# Sheet2.net
KiCad netlist of a schematic drawn in Altium Designer
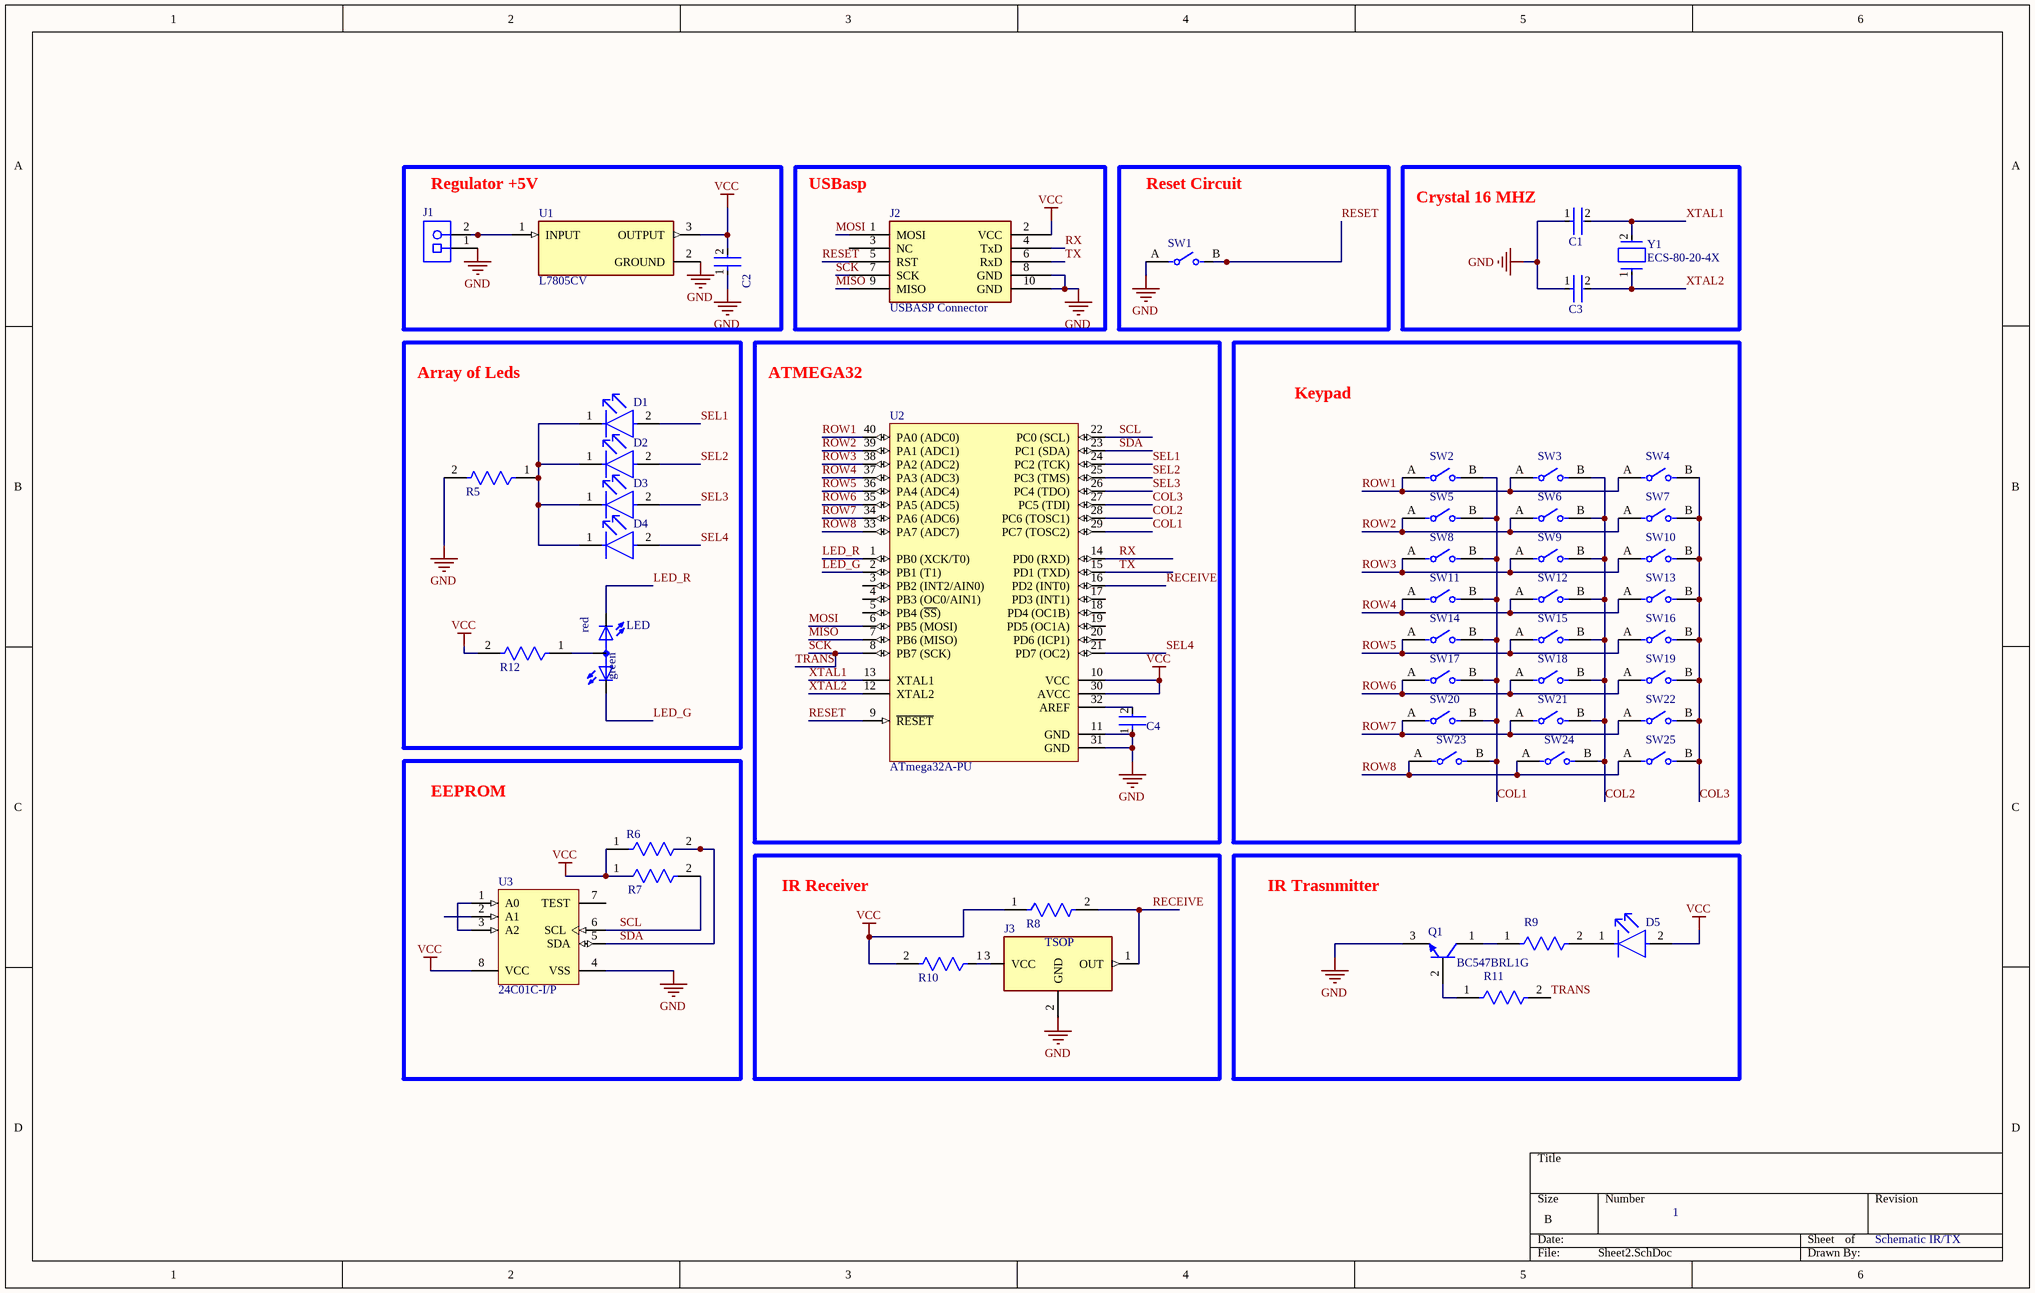
[diagram p0: Sheet2.SchDoc]

(export (version "E")
  (design (tool "Eeschema 10.0.6"))
  (components
    (comp (ref "C1")
      (value "K103K15X7RF5TL2")
      (footprint "FP-K155L2-MFG")
      (description "K103K15X7RF5TL2 Multilayer Ceramic Capacitor, 0.01 uF, 50 V, ± 10%, X7R, Radial Leaded (10P)")
      (fields (field (name "VOLTAGE") "50V") (field (name "TOLERANCE") "10%"))
      (libsource (lib "Altium Content Vault") (part "02cd4be3c70576c341d710602a673aa"))
    )
    (comp (ref "C2")
      (value "K103K15X7RF5TL2")
      (footprint "FP-K155L2-MFG")
      (description "K103K15X7RF5TL2 Multilayer Ceramic Capacitor, 0.01 uF, 50 V, ± 10%, X7R, Radial Leaded")
      (fields (field (name "VOLTAGE") "50V") (field (name "TOLERANCE") "10%"))
      (libsource (lib "Altium Content Vault") (part "02cd4be3c70576c341d710602a673aa"))
    )
    (comp (ref "C3")
      (value "K103K15X7RF5TL2")
      (footprint "FP-K155L2-MFG")
      (description "K103K15X7RF5TL2 Multilayer Ceramic Capacitor, 0.01 uF, 50 V, ± 10%, X7R, Radial Leaded (10P)")
      (fields (field (name "VOLTAGE") "50V") (field (name "TOLERANCE") "10%"))
      (libsource (lib "Altium Content Vault") (part "02cd4be3c70576c341d710602a673aa"))
    )
    (comp (ref "C4")
      (value "K103K15X7RF5TL2")
      (footprint "FP-K155L2-MFG")
      (description "K103K15X7RF5TL2 Multilayer Ceramic Capacitor, 0.01 uF, 50 V, ± 10%, X7R, Radial Leaded")
      (fields (field (name "VOLTAGE") "50V") (field (name "TOLERANCE") "10%"))
      (libsource (lib "Altium Content Vault") (part "02cd4be3c70576c341d710602a673aa"))
    )
    (comp (ref "D1")
      (value "TLLG4401")
      (footprint "FP-6_544-5255_01-4-MFG")
      (description "TLLG4401 LED, Green, 2mcd, 3mmDia., T-1, +/-25deg, 565nm, 7mA, 1.9V Vf, 20V Vr, 20mW, -40")
      (libsource (lib "Altium Content Vault") (part "8706943c75ba83719d021d2fdc84c58"))
    )
    (comp (ref "D2")
      (value "TLLG4401")
      (footprint "FP-6_544-5255_01-4-MFG")
      (description "TLLG4401 LED, Green, 2mcd, 3mmDia., T-1, +/-25deg, 565nm, 7mA, 1.9V Vf, 20V Vr, 20mW, -40")
      (libsource (lib "Altium Content Vault") (part "8706943c75ba83719d021d2fdc84c58"))
    )
    (comp (ref "D3")
      (value "TLLG4401")
      (footprint "FP-6_544-5255_01-4-MFG")
      (description "TLLG4401 LED, Green, 2mcd, 3mmDia., T-1, +/-25deg, 565nm, 7mA, 1.9V Vf, 20V Vr, 20mW, -40")
      (libsource (lib "Altium Content Vault") (part "8706943c75ba83719d021d2fdc84c58"))
    )
    (comp (ref "D4")
      (value "TLLG4401")
      (footprint "FP-6_544-5255_01-4-MFG")
      (description "TLLG4401 LED, Green, 2mcd, 3mmDia., T-1, +/-25deg, 565nm, 7mA, 1.9V Vf, 20V Vr, 20mW, -40")
      (libsource (lib "Altium Content Vault") (part "8706943c75ba83719d021d2fdc84c58"))
    )
    (comp (ref "D5")
      (value "TLLG4401")
      (footprint "FP-6_544-5255_01-4-MFG")
      (description "TLLG4401 LED, Green, 2mcd, 3mmDia., T-1, +/-25deg, 565nm, 7mA, 1.9V Vf, 20V Vr, 20mW, -40")
      (libsource (lib "Altium Content Vault") (part "8706943c75ba83719d021d2fdc84c58"))
    )
    (comp (ref "J1")
      (value "1729128")
      (footprint "PHOE-1729128-2_V")
      (description "Header of  Input Batt")
      (fields (field (name "MANUFACTURER") "Phoenix Contact"))
      (libsource (lib "Altium Content Vault") (part "CN-2P-F-R2"))
    )
    (comp (ref "J2")
      (value "USBASP Connector")
      (footprint "SamacSys:SHDR10W99P254_2X5_2032X889X927P")
      (description "Connector")
      (fields
        (field (name "MANUFACTURER_PART_NUMBER") "70246-1001")
        (field (name "MOUSER PART NUMBER") "538-70246-1001")
      )
      (libsource (lib "YoussifLIB") (part "USBASP Connector"))
    )
    (comp (ref "J3")
      (value "TSOP1838")
      (footprint "TSOP1838")
      (description "IR Remote Receiver 38KHz 35m 3-Pin")
      (fields (field (name "MF") "Vishay"))
      (libsource (lib "IR_Receiver") (part "TSOP1838"))
    )
    (comp (ref "LED")
      (value "L-59EGW-CA")
      (footprint "L-59EGW-CA")
      (description "LED; 5mm; bicolour; red/green; 5mcd; 5mcd; 60Â°; Front: convex; anode")
      (fields (field (name "MF") "Kingbright"))
      (libsource (lib "RG_LED") (part "L-59EGW-CA"))
    )
    (comp (ref "Q1")
      (value "BC547BRL1G")
      (footprint "ONSC-TO-92-3-29-11_AM_BL")
      (description "Amplifier Transistor, NPN Silicon, 3-Pin TO-92, Pb-Free, Tape and Reel")
      (fields (field (name "MANUFACTURER") "On Semiconductor"))
      (libsource (lib "Altium Content Vault") (part "ONSC-NPN-C1B2E3-3"))
    )
    (comp (ref "R5")
      (value "MRS25000C1001FCT00")
      (footprint "FP-MRS25-MFG")
      (description "RES 1K OHM 0.6W 1% AXIAL")
      (fields (field (name "TOLERANCE") "1%"))
      (libsource (lib "Altium Content Vault") (part "1029c3af85768c4190bb7ad29bc67b5"))
    )
    (comp (ref "R6")
      (value "MRS25000C1001FCT00")
      (footprint "FP-MRS25-MFG")
      (description "RES 1K OHM 0.6W 1% AXIAL")
      (fields (field (name "TOLERANCE") "1%"))
      (libsource (lib "Altium Content Vault") (part "1029c3af85768c4190bb7ad29bc67b5"))
    )
    (comp (ref "R7")
      (value "MRS25000C1001FCT00")
      (footprint "FP-MRS25-MFG")
      (description "RES 1K OHM 0.6W 1% AXIAL")
      (fields (field (name "TOLERANCE") "1%"))
      (libsource (lib "Altium Content Vault") (part "1029c3af85768c4190bb7ad29bc67b5"))
    )
    (comp (ref "R8")
      (value "MRS25000C1001FCT00")
      (footprint "FP-MRS25-MFG")
      (description "RES 1K OHM 0.6W 1% AXIAL")
      (fields (field (name "TOLERANCE") "1%"))
      (libsource (lib "Altium Content Vault") (part "1029c3af85768c4190bb7ad29bc67b5"))
    )
    (comp (ref "R9")
      (value "MRS25000C1001FCT00")
      (footprint "FP-MRS25-MFG")
      (description "RES 100 OHM 0.6W 1% AXIAL")
      (fields (field (name "TOLERANCE") "1%"))
      (libsource (lib "Altium Content Vault") (part "1029c3af85768c4190bb7ad29bc67b5"))
    )
    (comp (ref "R10")
      (value "MRS25000C1001FCT00")
      (footprint "FP-MRS25-MFG")
      (description "RES 100 OHM 0.6W 1% AXIAL")
      (fields (field (name "TOLERANCE") "1%"))
      (libsource (lib "Altium Content Vault") (part "1029c3af85768c4190bb7ad29bc67b5"))
    )
    (comp (ref "R11")
      (value "MRS25000C1001FCT00")
      (footprint "FP-MRS25-MFG")
      (description "RES 1K OHM 0.6W 1% AXIAL")
      (fields (field (name "TOLERANCE") "1%"))
      (libsource (lib "Altium Content Vault") (part "1029c3af85768c4190bb7ad29bc67b5"))
    )
    (comp (ref "R12")
      (value "MRS25000C1001FCT00")
      (footprint "FP-MRS25-MFG")
      (description "RES 1K OHM 0.6W 1% AXIAL")
      (fields (field (name "TOLERANCE") "1%"))
      (libsource (lib "Altium Content Vault") (part "1029c3af85768c4190bb7ad29bc67b5"))
    )
    (comp (ref "SW1")
      (value "EVQ-21505R")
      (footprint "FP-EVQ-21505R-MFG")
      (description "SWITCH TACTILE SPST-NO 0.02A 15V")
      (libsource (lib "Altium Content Vault") (part "2b0b2b19372efd94fa7681498149756"))
    )
    (comp (ref "SW2")
      (value "EVQ-21505R")
      (footprint "FP-EVQ-21505R-MFG")
      (description "SWITCH TACTILE SPST-NO 0.02A 15V")
      (libsource (lib "Altium Content Vault") (part "2b0b2b19372efd94fa7681498149756"))
    )
    (comp (ref "SW3")
      (value "EVQ-21505R")
      (footprint "FP-EVQ-21505R-MFG")
      (description "SWITCH TACTILE SPST-NO 0.02A 15V")
      (libsource (lib "Altium Content Vault") (part "2b0b2b19372efd94fa7681498149756"))
    )
    (comp (ref "SW4")
      (value "EVQ-21505R")
      (footprint "FP-EVQ-21505R-MFG")
      (description "SWITCH TACTILE SPST-NO 0.02A 15V")
      (libsource (lib "Altium Content Vault") (part "2b0b2b19372efd94fa7681498149756"))
    )
    (comp (ref "SW5")
      (value "EVQ-21505R")
      (footprint "FP-EVQ-21505R-MFG")
      (description "SWITCH TACTILE SPST-NO 0.02A 15V")
      (libsource (lib "Altium Content Vault") (part "2b0b2b19372efd94fa7681498149756"))
    )
    (comp (ref "SW6")
      (value "EVQ-21505R")
      (footprint "FP-EVQ-21505R-MFG")
      (description "SWITCH TACTILE SPST-NO 0.02A 15V")
      (libsource (lib "Altium Content Vault") (part "2b0b2b19372efd94fa7681498149756"))
    )
    (comp (ref "SW7")
      (value "EVQ-21505R")
      (footprint "FP-EVQ-21505R-MFG")
      (description "SWITCH TACTILE SPST-NO 0.02A 15V")
      (libsource (lib "Altium Content Vault") (part "2b0b2b19372efd94fa7681498149756"))
    )
    (comp (ref "SW8")
      (value "EVQ-21505R")
      (footprint "FP-EVQ-21505R-MFG")
      (description "SWITCH TACTILE SPST-NO 0.02A 15V")
      (libsource (lib "Altium Content Vault") (part "2b0b2b19372efd94fa7681498149756"))
    )
    (comp (ref "SW9")
      (value "EVQ-21505R")
      (footprint "FP-EVQ-21505R-MFG")
      (description "SWITCH TACTILE SPST-NO 0.02A 15V")
      (libsource (lib "Altium Content Vault") (part "2b0b2b19372efd94fa7681498149756"))
    )
    (comp (ref "SW10")
      (value "EVQ-21505R")
      (footprint "FP-EVQ-21505R-MFG")
      (description "SWITCH TACTILE SPST-NO 0.02A 15V")
      (libsource (lib "Altium Content Vault") (part "2b0b2b19372efd94fa7681498149756"))
    )
    (comp (ref "SW11")
      (value "EVQ-21505R")
      (footprint "FP-EVQ-21505R-MFG")
      (description "SWITCH TACTILE SPST-NO 0.02A 15V")
      (libsource (lib "Altium Content Vault") (part "2b0b2b19372efd94fa7681498149756"))
    )
    (comp (ref "SW12")
      (value "EVQ-21505R")
      (footprint "FP-EVQ-21505R-MFG")
      (description "SWITCH TACTILE SPST-NO 0.02A 15V")
      (libsource (lib "Altium Content Vault") (part "2b0b2b19372efd94fa7681498149756"))
    )
    (comp (ref "SW13")
      (value "EVQ-21505R")
      (footprint "FP-EVQ-21505R-MFG")
      (description "SWITCH TACTILE SPST-NO 0.02A 15V")
      (libsource (lib "Altium Content Vault") (part "2b0b2b19372efd94fa7681498149756"))
    )
    (comp (ref "SW14")
      (value "EVQ-21505R")
      (footprint "FP-EVQ-21505R-MFG")
      (description "SWITCH TACTILE SPST-NO 0.02A 15V")
      (libsource (lib "Altium Content Vault") (part "2b0b2b19372efd94fa7681498149756"))
    )
    (comp (ref "SW15")
      (value "EVQ-21505R")
      (footprint "FP-EVQ-21505R-MFG")
      (description "SWITCH TACTILE SPST-NO 0.02A 15V")
      (libsource (lib "Altium Content Vault") (part "2b0b2b19372efd94fa7681498149756"))
    )
    (comp (ref "SW16")
      (value "EVQ-21505R")
      (footprint "FP-EVQ-21505R-MFG")
      (description "SWITCH TACTILE SPST-NO 0.02A 15V")
      (libsource (lib "Altium Content Vault") (part "2b0b2b19372efd94fa7681498149756"))
    )
    (comp (ref "SW17")
      (value "EVQ-21505R")
      (footprint "FP-EVQ-21505R-MFG")
      (description "SWITCH TACTILE SPST-NO 0.02A 15V")
      (libsource (lib "Altium Content Vault") (part "2b0b2b19372efd94fa7681498149756"))
    )
    (comp (ref "SW18")
      (value "EVQ-21505R")
      (footprint "FP-EVQ-21505R-MFG")
      (description "SWITCH TACTILE SPST-NO 0.02A 15V")
      (libsource (lib "Altium Content Vault") (part "2b0b2b19372efd94fa7681498149756"))
    )
    (comp (ref "SW19")
      (value "EVQ-21505R")
      (footprint "FP-EVQ-21505R-MFG")
      (description "SWITCH TACTILE SPST-NO 0.02A 15V")
      (libsource (lib "Altium Content Vault") (part "2b0b2b19372efd94fa7681498149756"))
    )
    (comp (ref "SW20")
      (value "EVQ-21505R")
      (footprint "FP-EVQ-21505R-MFG")
      (description "SWITCH TACTILE SPST-NO 0.02A 15V")
      (libsource (lib "Altium Content Vault") (part "2b0b2b19372efd94fa7681498149756"))
    )
    (comp (ref "SW21")
      (value "EVQ-21505R")
      (footprint "FP-EVQ-21505R-MFG")
      (description "SWITCH TACTILE SPST-NO 0.02A 15V")
      (libsource (lib "Altium Content Vault") (part "2b0b2b19372efd94fa7681498149756"))
    )
    (comp (ref "SW22")
      (value "EVQ-21505R")
      (footprint "FP-EVQ-21505R-MFG")
      (description "SWITCH TACTILE SPST-NO 0.02A 15V")
      (libsource (lib "Altium Content Vault") (part "2b0b2b19372efd94fa7681498149756"))
    )
    (comp (ref "SW23")
      (value "EVQ-21505R")
      (footprint "FP-EVQ-21505R-MFG")
      (description "SWITCH TACTILE SPST-NO 0.02A 15V")
      (libsource (lib "Altium Content Vault") (part "2b0b2b19372efd94fa7681498149756"))
    )
    (comp (ref "SW24")
      (value "EVQ-21505R")
      (footprint "FP-EVQ-21505R-MFG")
      (description "SWITCH TACTILE SPST-NO 0.02A 15V")
      (libsource (lib "Altium Content Vault") (part "2b0b2b19372efd94fa7681498149756"))
    )
    (comp (ref "SW25")
      (value "EVQ-21505R")
      (footprint "FP-EVQ-21505R-MFG")
      (description "SWITCH TACTILE SPST-NO 0.02A 15V")
      (libsource (lib "Altium Content Vault") (part "2b0b2b19372efd94fa7681498149756"))
    )
    (comp (ref "U1")
      (value "L7805CV")
      (footprint "TO255P1040X460X1968-3")
      (description "Linear Voltage Regulator IC Positive Fixed 1 Output 1.5A TO-220")
      (fields (field (name "MF") "STMicroelectronics"))
      (libsource (lib "L7805CV") (part "L7805CV"))
    )
    (comp (ref "U2")
      (value "ATmega32A-PU")
      (footprint "40P6")
      (libsource (lib "Altium Content Vault") (part "MC-8B-AT16A-IL40"))
    )
    (comp (ref "U3")
      (value "24C01C-I/P")
      (footprint "PDIP300-P8")
      (description "1Kbit, 400kHz, 5V, I2C Serial EEPROM, 8-Pin PDIP, Industrial Temperature")
      (libsource (lib "Altium Content Vault") (part "MEM-SEEPROM-24C01-IL8"))
    )
    (comp (ref "Y1")
      (value "ECS-80-20-4X")
      (footprint "FP-ECS-80-20-4X-MFG")
      (fields (field (name "TOLERANCE") "0.003%"))
      (libsource (lib "Altium Content Vault") (part "c23a69dc6c9e2f18f2079038eb95dd1"))
    )
  )
  (nets
    (net (code "1") (name "/COL1") (class "Default")
      (node (ref "SW11") (pin "B") (pinfunction "B_B") (pintype "passive"))
      (node (ref "SW14") (pin "B") (pinfunction "B_B") (pintype "passive"))
      (node (ref "SW17") (pin "B") (pinfunction "B_B") (pintype "passive"))
      (node (ref "SW2") (pin "B") (pinfunction "B_B") (pintype "passive"))
      (node (ref "SW20") (pin "B") (pinfunction "B_B") (pintype "passive"))
      (node (ref "SW23") (pin "B") (pinfunction "B_B") (pintype "passive"))
      (node (ref "SW5") (pin "B") (pinfunction "B_B") (pintype "passive"))
      (node (ref "SW8") (pin "B") (pinfunction "B_B") (pintype "passive"))
      (node (ref "U2") (pin "29") (pinfunction "PC7_(TOSC2)_29") (pintype "bidirectional"))
    )
    (net (code "2") (name "/COL2") (class "Default")
      (node (ref "SW12") (pin "B") (pinfunction "B_B") (pintype "passive"))
      (node (ref "SW15") (pin "B") (pinfunction "B_B") (pintype "passive"))
      (node (ref "SW18") (pin "B") (pinfunction "B_B") (pintype "passive"))
      (node (ref "SW21") (pin "B") (pinfunction "B_B") (pintype "passive"))
      (node (ref "SW24") (pin "B") (pinfunction "B_B") (pintype "passive"))
      (node (ref "SW3") (pin "B") (pinfunction "B_B") (pintype "passive"))
      (node (ref "SW6") (pin "B") (pinfunction "B_B") (pintype "passive"))
      (node (ref "SW9") (pin "B") (pinfunction "B_B") (pintype "passive"))
      (node (ref "U2") (pin "28") (pinfunction "PC6_(TOSC1)_28") (pintype "bidirectional"))
    )
    (net (code "3") (name "/COL3") (class "Default")
      (node (ref "SW10") (pin "B") (pinfunction "B_B") (pintype "passive"))
      (node (ref "SW13") (pin "B") (pinfunction "B_B") (pintype "passive"))
      (node (ref "SW16") (pin "B") (pinfunction "B_B") (pintype "passive"))
      (node (ref "SW19") (pin "B") (pinfunction "B_B") (pintype "passive"))
      (node (ref "SW22") (pin "B") (pinfunction "B_B") (pintype "passive"))
      (node (ref "SW25") (pin "B") (pinfunction "B_B") (pintype "passive"))
      (node (ref "SW4") (pin "B") (pinfunction "B_B") (pintype "passive"))
      (node (ref "SW7") (pin "B") (pinfunction "B_B") (pintype "passive"))
      (node (ref "U2") (pin "27") (pinfunction "PC5_(TDI)_27") (pintype "bidirectional"))
    )
    (net (code "4") (name "/LED_G") (class "Default")
      (node (ref "LED") (pin "3") (pinfunction "CG_3") (pintype "passive"))
      (node (ref "U2") (pin "2") (pinfunction "PB1_(T1)_2") (pintype "bidirectional"))
    )
    (net (code "5") (name "/LED_R") (class "Default")
      (node (ref "LED") (pin "1") (pinfunction "CR_1") (pintype "passive"))
      (node (ref "U2") (pin "1") (pinfunction "PB0_(XCK/T0)_1") (pintype "bidirectional"))
    )
    (net (code "6") (name "/MISO") (class "Default")
      (node (ref "J2") (pin "9") (pinfunction "MISO_9") (pintype "passive"))
      (node (ref "U2") (pin "7") (pinfunction "PB6_(MISO)_7") (pintype "bidirectional"))
    )
    (net (code "7") (name "/MOSI") (class "Default")
      (node (ref "J2") (pin "1") (pinfunction "MOSI_1") (pintype "passive"))
      (node (ref "U2") (pin "6") (pinfunction "PB5_(MOSI)_6") (pintype "bidirectional"))
    )
    (net (code "8") (name "/RECEIVE") (class "Default")
      (node (ref "J3") (pin "1") (pinfunction "OUT_1") (pintype "output"))
      (node (ref "R8") (pin "2") (pinfunction "2_2") (pintype "passive"))
      (node (ref "U2") (pin "16") (pinfunction "PD2_(INT0)_16") (pintype "bidirectional"))
    )
    (net (code "9") (name "/RESET") (class "Default")
      (node (ref "J2") (pin "5") (pinfunction "RST_5") (pintype "passive"))
      (node (ref "SW1") (pin "B") (pinfunction "B_B") (pintype "passive"))
      (node (ref "U2") (pin "9") (pinfunction "~{RESET}_9") (pintype "input"))
    )
    (net (code "10") (name "/ROW1") (class "Default")
      (node (ref "SW2") (pin "A") (pinfunction "A_A") (pintype "passive"))
      (node (ref "SW3") (pin "A") (pinfunction "A_A") (pintype "passive"))
      (node (ref "SW4") (pin "A") (pinfunction "A_A") (pintype "passive"))
      (node (ref "U2") (pin "40") (pinfunction "PA0_(ADC0)_40") (pintype "bidirectional"))
    )
    (net (code "11") (name "/ROW2") (class "Default")
      (node (ref "SW5") (pin "A") (pinfunction "A_A") (pintype "passive"))
      (node (ref "SW6") (pin "A") (pinfunction "A_A") (pintype "passive"))
      (node (ref "SW7") (pin "A") (pinfunction "A_A") (pintype "passive"))
      (node (ref "U2") (pin "39") (pinfunction "PA1_(ADC1)_39") (pintype "bidirectional"))
    )
    (net (code "12") (name "/ROW3") (class "Default")
      (node (ref "SW10") (pin "A") (pinfunction "A_A") (pintype "passive"))
      (node (ref "SW8") (pin "A") (pinfunction "A_A") (pintype "passive"))
      (node (ref "SW9") (pin "A") (pinfunction "A_A") (pintype "passive"))
      (node (ref "U2") (pin "38") (pinfunction "PA2_(ADC2)_38") (pintype "bidirectional"))
    )
    (net (code "13") (name "/ROW4") (class "Default")
      (node (ref "SW11") (pin "A") (pinfunction "A_A") (pintype "passive"))
      (node (ref "SW12") (pin "A") (pinfunction "A_A") (pintype "passive"))
      (node (ref "SW13") (pin "A") (pinfunction "A_A") (pintype "passive"))
      (node (ref "U2") (pin "37") (pinfunction "PA3_(ADC3)_37") (pintype "bidirectional"))
    )
    (net (code "14") (name "/ROW5") (class "Default")
      (node (ref "SW14") (pin "A") (pinfunction "A_A") (pintype "passive"))
      (node (ref "SW15") (pin "A") (pinfunction "A_A") (pintype "passive"))
      (node (ref "SW16") (pin "A") (pinfunction "A_A") (pintype "passive"))
      (node (ref "U2") (pin "36") (pinfunction "PA4_(ADC4)_36") (pintype "bidirectional"))
    )
    (net (code "15") (name "/ROW6") (class "Default")
      (node (ref "SW17") (pin "A") (pinfunction "A_A") (pintype "passive"))
      (node (ref "SW18") (pin "A") (pinfunction "A_A") (pintype "passive"))
      (node (ref "SW19") (pin "A") (pinfunction "A_A") (pintype "passive"))
      (node (ref "U2") (pin "35") (pinfunction "PA5_(ADC5)_35") (pintype "bidirectional"))
    )
    (net (code "16") (name "/ROW7") (class "Default")
      (node (ref "SW20") (pin "A") (pinfunction "A_A") (pintype "passive"))
      (node (ref "SW21") (pin "A") (pinfunction "A_A") (pintype "passive"))
      (node (ref "SW22") (pin "A") (pinfunction "A_A") (pintype "passive"))
      (node (ref "U2") (pin "34") (pinfunction "PA6_(ADC6)_34") (pintype "bidirectional"))
    )
    (net (code "17") (name "/ROW8") (class "Default")
      (node (ref "SW23") (pin "A") (pinfunction "A_A") (pintype "passive"))
      (node (ref "SW24") (pin "A") (pinfunction "A_A") (pintype "passive"))
      (node (ref "SW25") (pin "A") (pinfunction "A_A") (pintype "passive"))
      (node (ref "U2") (pin "33") (pinfunction "PA7_(ADC7)_33") (pintype "bidirectional"))
    )
    (net (code "18") (name "/RX") (class "Default")
      (node (ref "J2") (pin "4") (pinfunction "TxD_4") (pintype "passive"))
      (node (ref "U2") (pin "14") (pinfunction "PD0_(RXD)_14") (pintype "bidirectional"))
    )
    (net (code "19") (name "/SCK") (class "Default")
      (node (ref "J2") (pin "7") (pinfunction "SCK_7") (pintype "passive"))
      (node (ref "R11") (pin "2") (pinfunction "2_2") (pintype "passive"))
      (node (ref "U2") (pin "8") (pinfunction "PB7_(SCK)_8") (pintype "bidirectional"))
    )
    (net (code "20") (name "/SCL") (class "Default")
      (node (ref "R7") (pin "2") (pinfunction "2_2") (pintype "passive"))
      (node (ref "U2") (pin "22") (pinfunction "PC0_(SCL)_22") (pintype "bidirectional"))
      (node (ref "U3") (pin "6") (pinfunction "SCL_6") (pintype "input"))
    )
    (net (code "21") (name "/SDA") (class "Default")
      (node (ref "R6") (pin "2") (pinfunction "2_2") (pintype "passive"))
      (node (ref "U2") (pin "23") (pinfunction "PC1_(SDA)_23") (pintype "bidirectional"))
      (node (ref "U3") (pin "5") (pinfunction "SDA_5") (pintype "bidirectional"))
    )
    (net (code "22") (name "/SEL1") (class "Default")
      (node (ref "D1") (pin "2") (pinfunction "A_2") (pintype "passive"))
      (node (ref "U2") (pin "24") (pinfunction "PC2_(TCK)_24") (pintype "bidirectional"))
    )
    (net (code "23") (name "/SEL2") (class "Default")
      (node (ref "D2") (pin "2") (pinfunction "A_2") (pintype "passive"))
      (node (ref "U2") (pin "25") (pinfunction "PC3_(TMS)_25") (pintype "bidirectional"))
    )
    (net (code "24") (name "/SEL3") (class "Default")
      (node (ref "D3") (pin "2") (pinfunction "A_2") (pintype "passive"))
      (node (ref "U2") (pin "26") (pinfunction "PC4_(TDO)_26") (pintype "bidirectional"))
    )
    (net (code "25") (name "/SEL4") (class "Default")
      (node (ref "D4") (pin "2") (pinfunction "A_2") (pintype "passive"))
      (node (ref "U2") (pin "21") (pinfunction "PD7_(OC2)_21") (pintype "bidirectional"))
    )
    (net (code "26") (name "/TX") (class "Default")
      (node (ref "J2") (pin "6") (pinfunction "RxD_6") (pintype "passive"))
      (node (ref "U2") (pin "15") (pinfunction "PD1_(TXD)_15") (pintype "bidirectional"))
    )
    (net (code "27") (name "/XTAL1") (class "Default")
      (node (ref "C1") (pin "2") (pinfunction "2_2") (pintype "passive"))
      (node (ref "U2") (pin "13") (pinfunction "XTAL1_13") (pintype "passive"))
      (node (ref "Y1") (pin "2") (pinfunction "2_2") (pintype "passive"))
    )
    (net (code "28") (name "/XTAL2") (class "Default")
      (node (ref "C3") (pin "2") (pinfunction "2_2") (pintype "passive"))
      (node (ref "U2") (pin "12") (pinfunction "XTAL2_12") (pintype "passive"))
      (node (ref "Y1") (pin "1") (pinfunction "1_1") (pintype "passive"))
    )
    (net (code "29") (name "GND") (class "Default")
      (node (ref "C1") (pin "1") (pinfunction "1_1") (pintype "passive"))
      (node (ref "C2") (pin "1") (pinfunction "1_1") (pintype "passive"))
      (node (ref "C3") (pin "1") (pinfunction "1_1") (pintype "passive"))
      (node (ref "C4") (pin "1") (pinfunction "1_1") (pintype "passive"))
      (node (ref "J1") (pin "1") (pinfunction "1_1") (pintype "passive"))
      (node (ref "J2") (pin "10") (pinfunction "GND_10") (pintype "passive"))
      (node (ref "J2") (pin "8") (pinfunction "GND_8") (pintype "passive"))
      (node (ref "J3") (pin "2") (pinfunction "GND_2") (pintype "power_in"))
      (node (ref "Q1") (pin "3") (pinfunction "E_3") (pintype "passive"))
      (node (ref "R5") (pin "2") (pinfunction "2_2") (pintype "passive"))
      (node (ref "SW1") (pin "A") (pinfunction "A_A") (pintype "passive"))
      (node (ref "U1") (pin "2") (pinfunction "GROUND_2") (pintype "power_in"))
      (node (ref "U2") (pin "11") (pinfunction "GND_11") (pintype "power_in"))
      (node (ref "U2") (pin "31") (pinfunction "GND_31") (pintype "power_in"))
      (node (ref "U3") (pin "4") (pinfunction "VSS_4") (pintype "power_in"))
    )
    (net (code "30") (name "Net-(D1-C)") (class "Default")
      (node (ref "D1") (pin "1") (pinfunction "C_1") (pintype "passive"))
      (node (ref "D2") (pin "1") (pinfunction "C_1") (pintype "passive"))
      (node (ref "D3") (pin "1") (pinfunction "C_1") (pintype "passive"))
      (node (ref "D4") (pin "1") (pinfunction "C_1") (pintype "passive"))
      (node (ref "R5") (pin "1") (pinfunction "1_1") (pintype "passive"))
    )
    (net (code "31") (name "Net-(D5-C)") (class "Default")
      (node (ref "D5") (pin "1") (pinfunction "C_1") (pintype "passive"))
      (node (ref "R9") (pin "2") (pinfunction "2_2") (pintype "passive"))
    )
    (net (code "32") (name "Net-(J3-VCC)") (class "Default")
      (node (ref "J3") (pin "3") (pinfunction "VCC_3") (pintype "power_in"))
      (node (ref "R10") (pin "1") (pinfunction "1_1") (pintype "passive"))
    )
    (net (code "33") (name "Net-(LED-A)") (class "Default")
      (node (ref "LED") (pin "2") (pinfunction "A_2") (pintype "passive"))
      (node (ref "R12") (pin "1") (pinfunction "1_1") (pintype "passive"))
    )
    (net (code "34") (name "Net-(Q1-B)") (class "Default")
      (node (ref "Q1") (pin "2") (pinfunction "B_2") (pintype "passive"))
      (node (ref "R11") (pin "1") (pinfunction "1_1") (pintype "passive"))
    )
    (net (code "35") (name "Net-(Q1-C)") (class "Default")
      (node (ref "Q1") (pin "1") (pinfunction "C_1") (pintype "passive"))
      (node (ref "R9") (pin "1") (pinfunction "1_1") (pintype "passive"))
    )
    (net (code "36") (name "Net-(U1-INPUT)") (class "Default")
      (node (ref "J1") (pin "2") (pinfunction "2_2") (pintype "passive"))
      (node (ref "U1") (pin "1") (pinfunction "INPUT_1") (pintype "input"))
    )
    (net (code "37") (name "Net-(U2-AREF)") (class "Default")
      (node (ref "C4") (pin "2") (pinfunction "2_2") (pintype "passive"))
      (node (ref "U2") (pin "32") (pinfunction "AREF_32") (pintype "power_in"))
    )
    (net (code "38") (name "Net-(U3-A0)") (class "Default")
      (node (ref "U3") (pin "1") (pinfunction "A0_1") (pintype "input"))
      (node (ref "U3") (pin "3") (pinfunction "A2_3") (pintype "input"))
    )
    (net (code "39") (name "VCC") (class "Default")
      (node (ref "C2") (pin "2") (pinfunction "2_2") (pintype "passive"))
      (node (ref "D5") (pin "2") (pinfunction "A_2") (pintype "passive"))
      (node (ref "J2") (pin "2") (pinfunction "VCC_2") (pintype "passive"))
      (node (ref "R10") (pin "2") (pinfunction "2_2") (pintype "passive"))
      (node (ref "R12") (pin "2") (pinfunction "2_2") (pintype "passive"))
      (node (ref "R6") (pin "1") (pinfunction "1_1") (pintype "passive"))
      (node (ref "R7") (pin "1") (pinfunction "1_1") (pintype "passive"))
      (node (ref "R8") (pin "1") (pinfunction "1_1") (pintype "passive"))
      (node (ref "U1") (pin "3") (pinfunction "OUTPUT_3") (pintype "output"))
      (node (ref "U2") (pin "10") (pinfunction "VCC_10") (pintype "power_in"))
      (node (ref "U2") (pin "30") (pinfunction "AVCC_30") (pintype "power_in"))
      (node (ref "U3") (pin "8") (pinfunction "VCC_8") (pintype "power_in"))
    )
    (net (code "40") (name "unconnected-(J2-NC-Pad3)") (class "Default")
      (node (ref "J2") (pin "3") (pinfunction "NC_3") (pintype "passive"))
    )
    (net (code "41") (name "unconnected-(U2-PB2_(INT2{slash}AIN0)-Pad3)") (class "Default")
      (node (ref "U2") (pin "3") (pinfunction "PB2_(INT2/AIN0)_3") (pintype "bidirectional"))
    )
    (net (code "42") (name "unconnected-(U2-PB3_(OC0{slash}AIN1)-Pad4)") (class "Default")
      (node (ref "U2") (pin "4") (pinfunction "PB3_(OC0/AIN1)_4") (pintype "bidirectional"))
    )
    (net (code "43") (name "unconnected-(U2-PB4_(~{SS})-Pad5)") (class "Default")
      (node (ref "U2") (pin "5") (pinfunction "PB4_(~{SS})_5") (pintype "bidirectional"))
    )
    (net (code "44") (name "unconnected-(U2-PD3_(INT1)-Pad17)") (class "Default")
      (node (ref "U2") (pin "17") (pinfunction "PD3_(INT1)_17") (pintype "bidirectional"))
    )
    (net (code "45") (name "unconnected-(U2-PD4_(OC1B)-Pad18)") (class "Default")
      (node (ref "U2") (pin "18") (pinfunction "PD4_(OC1B)_18") (pintype "bidirectional"))
    )
    (net (code "46") (name "unconnected-(U2-PD5_(OC1A)-Pad19)") (class "Default")
      (node (ref "U2") (pin "19") (pinfunction "PD5_(OC1A)_19") (pintype "bidirectional"))
    )
    (net (code "47") (name "unconnected-(U2-PD6_(ICP1)-Pad20)") (class "Default")
      (node (ref "U2") (pin "20") (pinfunction "PD6_(ICP1)_20") (pintype "bidirectional"))
    )
    (net (code "48") (name "unconnected-(U3-A1-Pad2)") (class "Default")
      (node (ref "U3") (pin "2") (pinfunction "A1_2") (pintype "input"))
    )
    (net (code "49") (name "unconnected-(U3-TEST-Pad7)") (class "Default")
      (node (ref "U3") (pin "7") (pinfunction "TEST_7") (pintype "passive"))
    )
  )
)
